# battery_diode-discharging.net
KiCad netlist of a schematic drawn in Altium Designer
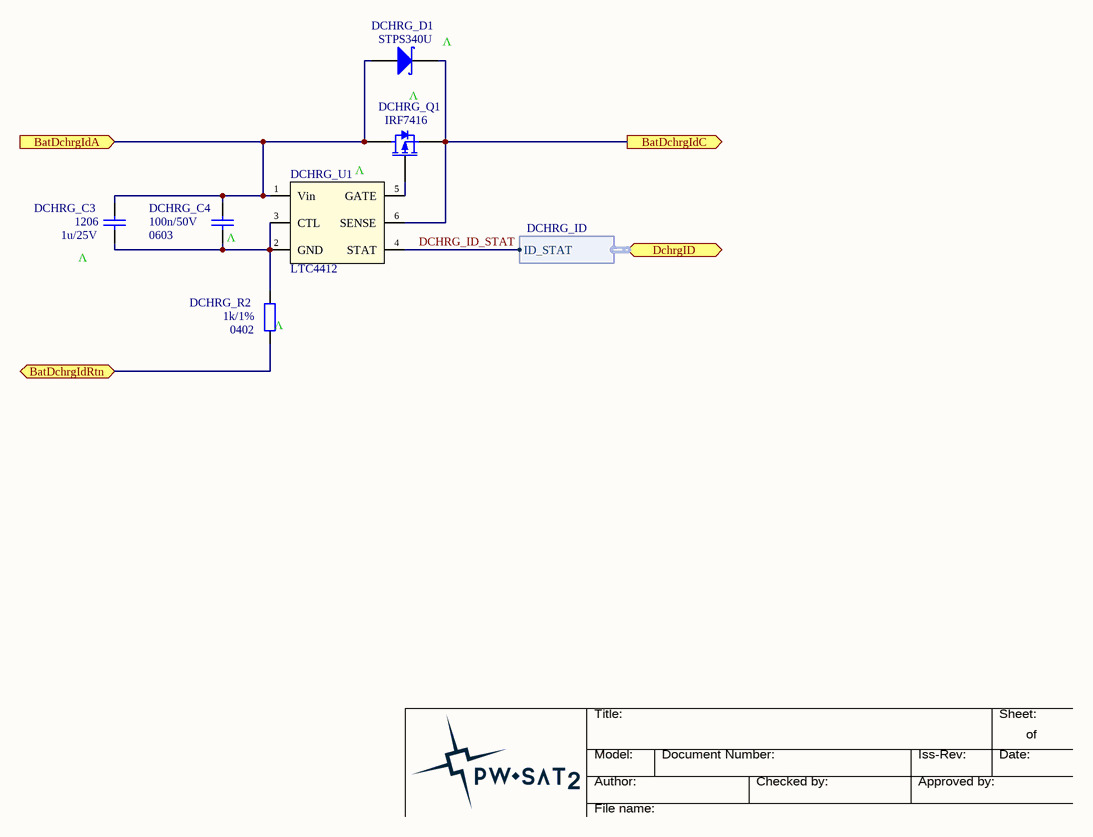
[diagram p0: battery_diode-discharging.SchDoc]

(export (version "E")
  (design (tool "Eeschema 10.0.6"))
  (components
    (comp (ref "DCHRG_C3")
      (value "1u/25V")
      (footprint "SMD_Capacitor_1206")
      (description "Ceramic Cap Kemet COTS 1u/25V X7R 1206")
      (fields
        (field (name "MANUFACTURERPARTNUMBER") "C1206T105K3RALTU")
        (field (name "MANUFACTURER") "Kemet")
        (field (name "PACKAGE") "1206")
      )
      (libsource (lib "capacitors") (part "Cer_C1206T105K3RALTU"))
    )
    (comp (ref "DCHRG_C4")
      (value "100n/50V")
      (footprint "SMD_Capacitor_0603")
      (description "Ceramic Cap Murata Automotive 100n/50V X7R 0603")
      (fields
        (field (name "MANUFACTURER") "Murata")
        (field (name "MANUFACTURERPARTNUMBER") "GCJ188R71H104KA12D")
        (field (name "PACKAGE") "0603")
      )
      (libsource (lib "capacitors") (part "Cer_GCJ188R71H104KA12D"))
    )
    (comp (ref "DCHRG_D1")
      (value "STPS340U")
      (footprint "DO-214AA")
      (description "3A/40V Power Schottky Rectifier.")
      (fields (field (name "MANUFACTURER") "STMicroelectronics"))
      (libsource (lib "diodes") (part "STPS340x"))
    )
    (comp (ref "DCHRG_Q1")
      (value "IRF7416")
      (footprint "SOIC-8-N_SSSGDDDD")
      (description "10A/30V HEXFET Power P-MOSFET.")
      (fields (field (name "MANUFACTURER") "International Rectifier"))
      (libsource (lib "transistors") (part "IRF7416"))
    )
    (comp (ref "DCHRG_R2")
      (value "1k/1%")
      (footprint "SMD_Resistor_0402")
      (description "1k/1% Vishay CRCW 0402 Resistor. 63mW, 100ppm, 50V.")
      (fields
        (field (name "MANUFACTURER") "Vishay")
        (field (name "MANUFACTURERPARTNUMBER") "CRCW04021K00FKxxxx")
        (field (name "PACKAGE") "0402")
      )
      (libsource (lib "resistors") (part "CRCW04021K00FKxxxx"))
    )
    (comp (ref "DCHRG_U1")
      (value "LTC4412")
      (footprint "SOT23-6")
      (description "Ideal Diode, Low Loss PowerPath Controller.")
      (fields (field (name "MANUFACTURER") "Linear Technology"))
      (libsource (lib "microcircuits") (part "LTC4412"))
    )
  )
  (nets
    (net (code "2") (name "/BatDchrgIdA") (class "Default")
      (node (ref "DCHRG_C3") (pin "1") (pinfunction "1_1") (pintype "passive"))
      (node (ref "DCHRG_C4") (pin "1") (pinfunction "1_1") (pintype "passive"))
      (node (ref "DCHRG_D1") (pin "A") (pinfunction "A_A") (pintype "passive"))
      (node (ref "DCHRG_Q1") (pin "D") (pinfunction "D_D") (pintype "passive"))
      (node (ref "DCHRG_U1") (pin "1") (pinfunction "Vin_1") (pintype "passive"))
    )
    (net (code "3") (name "/BatDchrgIdC") (class "Default")
      (node (ref "DCHRG_D1") (pin "K") (pinfunction "K_K") (pintype "passive"))
      (node (ref "DCHRG_Q1") (pin "S") (pinfunction "S_S") (pintype "passive"))
      (node (ref "DCHRG_U1") (pin "6") (pinfunction "SENSE_6") (pintype "passive"))
    )
    (net (code "4") (name "/BatDchrgIdRtn") (class "Default")
      (node (ref "DCHRG_R2") (pin "2") (pinfunction "2_2") (pintype "passive"))
    )
    (net (code "5") (name "/DCHRG_ID_STAT") (class "Default")
      (node (ref "DCHRG_U1") (pin "4") (pinfunction "STAT_4") (pintype "passive"))
    )
    (net (code "7") (name "Net-(DCHRG_U1-CTL)") (class "Default")
      (node (ref "DCHRG_C3") (pin "2") (pinfunction "2_2") (pintype "passive"))
      (node (ref "DCHRG_C4") (pin "2") (pinfunction "2_2") (pintype "passive"))
      (node (ref "DCHRG_R2") (pin "1") (pinfunction "1_1") (pintype "passive"))
      (node (ref "DCHRG_U1") (pin "2") (pinfunction "GND_2") (pintype "passive"))
      (node (ref "DCHRG_U1") (pin "3") (pinfunction "CTL_3") (pintype "passive"))
    )
    (net (code "8") (name "Net-(DCHRG_U1-GATE)") (class "Default")
      (node (ref "DCHRG_Q1") (pin "G") (pinfunction "G_G") (pintype "passive"))
      (node (ref "DCHRG_U1") (pin "5") (pinfunction "GATE_5") (pintype "passive"))
    )
  )
)
